# ESP32_SensorShield.net
KiCad netlist of a schematic drawn in EAGLE
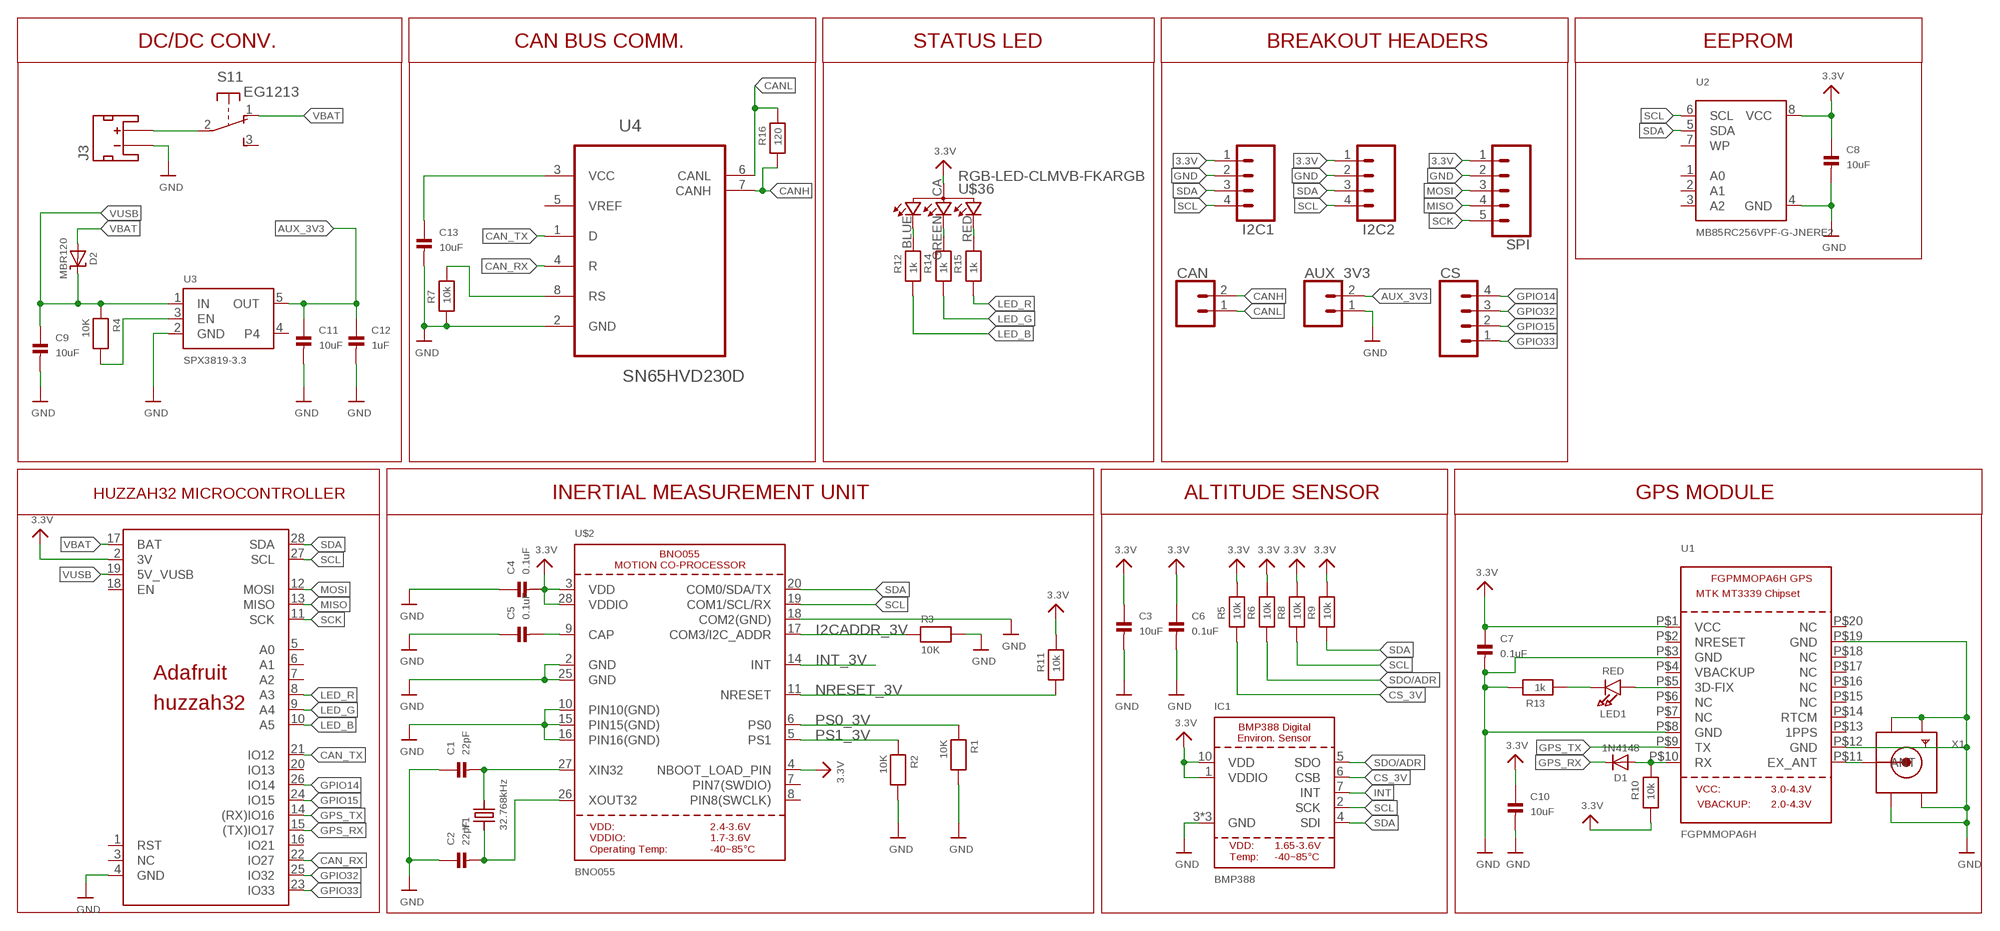
[diagram p0: schematic, sheet 1]

(export (version "E")
  (design (tool "Eeschema 10.0.6"))
  (components
    (comp (ref "AUX_3V3")
      (value "CONN_02")
      (footprint "eagle-import:1X02")
      (libsource (lib "eagle-import") (part "CONN_02"))
    )
    (comp (ref "C1")
      (value "22pF")
      (footprint "eagle-import:0603")
      (libsource (lib "eagle-import") (part "CAP_CERAMIC0603"))
    )
    (comp (ref "C2")
      (value "22pF")
      (footprint "eagle-import:0603")
      (libsource (lib "eagle-import") (part "CAP_CERAMIC0603"))
    )
    (comp (ref "C3")
      (value "10uF")
      (footprint "eagle-import:0805")
      (libsource (lib "eagle-import") (part "CAP_CERAMIC0805"))
    )
    (comp (ref "C4")
      (value "0.1uF")
      (footprint "eagle-import:0603")
      (libsource (lib "eagle-import") (part "CAP_CERAMIC0603"))
    )
    (comp (ref "C5")
      (value "0.1uF")
      (footprint "eagle-import:0603")
      (libsource (lib "eagle-import") (part "CAP_CERAMIC0603"))
    )
    (comp (ref "C6")
      (value "0.1uF")
      (footprint "eagle-import:0603")
      (libsource (lib "eagle-import") (part "CAP_CERAMIC0603"))
    )
    (comp (ref "C7")
      (value "0.1uF")
      (footprint "eagle-import:0603")
      (libsource (lib "eagle-import") (part "CAP_CERAMIC0603"))
    )
    (comp (ref "C8")
      (value "10uF")
      (footprint "eagle-import:0805")
      (libsource (lib "eagle-import") (part "CAP_CERAMIC0805"))
    )
    (comp (ref "C9")
      (value "10uF")
      (footprint "eagle-import:0805")
      (libsource (lib "eagle-import") (part "CAP_CERAMIC0805"))
    )
    (comp (ref "C10")
      (value "10uF")
      (footprint "eagle-import:0805")
      (libsource (lib "eagle-import") (part "CAP_CERAMIC0805"))
    )
    (comp (ref "C11")
      (value "10uF")
      (footprint "eagle-import:0805")
      (libsource (lib "eagle-import") (part "CAP_CERAMIC0805"))
    )
    (comp (ref "C12")
      (value "1uF")
      (footprint "eagle-import:0805")
      (libsource (lib "eagle-import") (part "CAP_CERAMIC0805"))
    )
    (comp (ref "C13")
      (value "10uF")
      (footprint "eagle-import:0805")
      (libsource (lib "eagle-import") (part "CAP_CERAMIC0805"))
    )
    (comp (ref "CAN")
      (value "CONN_02")
      (footprint "eagle-import:1X02")
      (libsource (lib "eagle-import") (part "CONN_02"))
    )
    (comp (ref "CS")
      (value "CONN_04")
      (footprint "eagle-import:1X04")
      (libsource (lib "eagle-import") (part "CONN_04"))
    )
    (comp (ref "D1")
      (value "1N4148")
      (footprint "eagle-import:SOD-323")
      (libsource (lib "eagle-import") (part "DIODESOD-323"))
    )
    (comp (ref "D2")
      (value "MBR120")
      (footprint "eagle-import:SOD-123")
      (libsource (lib "eagle-import") (part "DIODE-SCHOTTKYSOD-123"))
    )
    (comp (ref "I2C1")
      (value "CONN_04")
      (footprint "eagle-import:1X04")
      (libsource (lib "eagle-import") (part "CONN_04"))
    )
    (comp (ref "I2C2")
      (value "CONN_04")
      (footprint "eagle-import:1X04")
      (libsource (lib "eagle-import") (part "CONN_04"))
    )
    (comp (ref "IC1")
      (value "BMP388")
      (footprint "eagle-import:BMP388")
      (libsource (lib "eagle-import") (part "BMP388"))
    )
    (comp (ref "J3")
      (value "JST_2MM_MALE")
      (footprint "eagle-import:JST-2-SMD")
      (libsource (lib "eagle-import") (part "JST_2MM_MALE"))
    )
    (comp (ref "LED1")
      (value "RED")
      (footprint "eagle-import:CHIPLED_0805")
      (libsource (lib "eagle-import") (part "LED0805"))
    )
    (comp (ref "R1")
      (value "10K")
      (footprint "eagle-import:0603")
      (libsource (lib "eagle-import") (part "RESISTOR0603"))
    )
    (comp (ref "R2")
      (value "10K")
      (footprint "eagle-import:0603")
      (libsource (lib "eagle-import") (part "RESISTOR0603"))
    )
    (comp (ref "R3")
      (value "10K")
      (footprint "eagle-import:0603")
      (libsource (lib "eagle-import") (part "RESISTOR0603"))
    )
    (comp (ref "R4")
      (value "10K")
      (footprint "eagle-import:0603")
      (libsource (lib "eagle-import") (part "RESISTOR0603"))
    )
    (comp (ref "R5")
      (value "10k")
      (footprint "eagle-import:0603")
      (libsource (lib "eagle-import") (part "RESISTOR0603"))
    )
    (comp (ref "R6")
      (value "10k")
      (footprint "eagle-import:0603")
      (libsource (lib "eagle-import") (part "RESISTOR0603"))
    )
    (comp (ref "R7")
      (value "10k")
      (footprint "eagle-import:0603")
      (libsource (lib "eagle-import") (part "RESISTOR0603"))
    )
    (comp (ref "R8")
      (value "10k")
      (footprint "eagle-import:0603")
      (libsource (lib "eagle-import") (part "RESISTOR0603"))
    )
    (comp (ref "R9")
      (value "10k")
      (footprint "eagle-import:0603")
      (libsource (lib "eagle-import") (part "RESISTOR0603"))
    )
    (comp (ref "R10")
      (value "10k")
      (footprint "eagle-import:0603")
      (libsource (lib "eagle-import") (part "RESISTOR0603"))
    )
    (comp (ref "R11")
      (value "10k")
      (footprint "eagle-import:0603")
      (libsource (lib "eagle-import") (part "RESISTOR0603"))
    )
    (comp (ref "R12")
      (value "1k")
      (footprint "eagle-import:0603")
      (libsource (lib "eagle-import") (part "RESISTOR0603"))
    )
    (comp (ref "R13")
      (value "1k")
      (footprint "eagle-import:0603")
      (libsource (lib "eagle-import") (part "RESISTOR0603"))
    )
    (comp (ref "R14")
      (value "1k")
      (footprint "eagle-import:0603")
      (libsource (lib "eagle-import") (part "RESISTOR0603"))
    )
    (comp (ref "R15")
      (value "1k")
      (footprint "eagle-import:0603")
      (libsource (lib "eagle-import") (part "RESISTOR0603"))
    )
    (comp (ref "R16")
      (value "120")
      (footprint "eagle-import:0603")
      (libsource (lib "eagle-import") (part "RESISTOR0603"))
    )
    (comp (ref "S1")
      (value "EG1213")
      (footprint "eagle-import:EG1213")
      (libsource (lib "eagle-import") (part "EG1213"))
    )
    (comp (ref "SPI")
      (value "CONN_05")
      (footprint "eagle-import:1X05")
      (libsource (lib "eagle-import") (part "CONN_05"))
    )
    (comp (ref "U$1")
      (value "ADAFRUIT-FEATHER-HUZZAH32-SHIELD")
      (footprint "eagle-import:ADAFRUIT-FEATHER-HUZZAH32-SHIELD")
      (libsource (lib "eagle-import") (part "ADAFRUIT-FEATHER-HUZZAH32-SHIELD"))
    )
    (comp (ref "U$2")
      (value "BNO055")
      (footprint "eagle-import:BNO055")
      (libsource (lib "eagle-import") (part "BNO055"))
    )
    (comp (ref "U$36")
      (value "RGB-LED-CLMVB-FKARGB")
      (footprint "eagle-import:PLCC4-2MM-RGB")
      (libsource (lib "eagle-import") (part "RGB-LED-CLMVB-FKARGB"))
    )
    (comp (ref "U1")
      (value "FGPMMOPA6H")
      (footprint "eagle-import:FGPMMOPA6H")
      (libsource (lib "eagle-import") (part "GPS_FGPMMOPA6H"))
    )
    (comp (ref "U2")
      (value "MB85RC256VPF-G-JNERE2")
      (footprint "eagle-import:SOIC8_208MIL")
      (libsource (lib "eagle-import") (part "FRAM_SOIC8_I2C"))
    )
    (comp (ref "U3")
      (value "SPX3819-3.3")
      (footprint "eagle-import:SOT23-5")
      (libsource (lib "eagle-import") (part "VREG_SOT23-5"))
    )
    (comp (ref "U4")
      (value "SN65HVD230D")
      (footprint "eagle-import:SOIC127P600X175-8N")
      (fields (field (name "MF") "Texas Instruments"))
      (libsource (lib "eagle-import") (part "SN65HVD230D"))
    )
    (comp (ref "X1")
      (value "SMACONNECTOR_EDGE")
      (footprint "eagle-import:SMA_EDGELAUNCH")
      (libsource (lib "eagle-import") (part "SMACONNECTOR_EDGE"))
    )
    (comp (ref "Y1")
      (value "32.768kHz")
      (footprint "eagle-import:CRYSTAL_8X3.8")
      (libsource (lib "eagle-import") (part "CRYSTAL8.0X3.8"))
    )
  )
  (nets
    (net (code "1") (name "/I2CADDR_3V") (class "Default")
      (node (ref "R3") (pin "1") (pinfunction "1_1") (pintype "passive"))
      (node (ref "U$2") (pin "17") (pinfunction "COM3/I2C_ADDR_17") (pintype "bidirectional"))
    )
    (net (code "2") (name "/INT_3V") (class "Default")
      (node (ref "U$2") (pin "14") (pinfunction "INT_14") (pintype "output"))
    )
    (net (code "3") (name "/NRESET_3V") (class "Default")
      (node (ref "R11") (pin "1") (pinfunction "1_1") (pintype "passive"))
      (node (ref "U$2") (pin "11") (pinfunction "NRESET_11") (pintype "bidirectional"))
    )
    (net (code "4") (name "/PS0_3V") (class "Default")
      (node (ref "R1") (pin "1") (pinfunction "1_1") (pintype "passive"))
      (node (ref "U$2") (pin "6") (pinfunction "PS0_6") (pintype "input"))
    )
    (net (code "5") (name "/PS1_3V") (class "Default")
      (node (ref "R2") (pin "1") (pinfunction "1_1") (pintype "passive"))
      (node (ref "U$2") (pin "5") (pinfunction "PS1_5") (pintype "input"))
    )
    (net (code "6") (name "3.3V") (class "Default")
      (node (ref "C10") (pin "1") (pinfunction "P$1_1") (pintype "passive"))
      (node (ref "C3") (pin "1") (pinfunction "P$1_1") (pintype "passive"))
      (node (ref "C4") (pin "2") (pinfunction "P$2_2") (pintype "passive"))
      (node (ref "C6") (pin "1") (pinfunction "P$1_1") (pintype "passive"))
      (node (ref "C7") (pin "1") (pinfunction "P$1_1") (pintype "passive"))
      (node (ref "C8") (pin "1") (pinfunction "P$1_1") (pintype "passive"))
      (node (ref "I2C1") (pin "1") (pinfunction "1_1") (pintype "passive"))
      (node (ref "I2C2") (pin "1") (pinfunction "1_1") (pintype "passive"))
      (node (ref "IC1") (pin "1") (pinfunction "VDDIO_1") (pintype "power_in"))
      (node (ref "IC1") (pin "10") (pinfunction "VDD_10") (pintype "power_in"))
      (node (ref "R10") (pin "1") (pinfunction "1_1") (pintype "passive"))
      (node (ref "R11") (pin "2") (pinfunction "2_2") (pintype "passive"))
      (node (ref "R5") (pin "2") (pinfunction "2_2") (pintype "passive"))
      (node (ref "R6") (pin "2") (pinfunction "2_2") (pintype "passive"))
      (node (ref "R8") (pin "2") (pinfunction "2_2") (pintype "passive"))
      (node (ref "R9") (pin "2") (pinfunction "2_2") (pintype "passive"))
      (node (ref "SPI") (pin "1") (pinfunction "1_1") (pintype "passive"))
      (node (ref "U$1") (pin "2") (pinfunction "3V_2") (pintype "bidirectional"))
      (node (ref "U$2") (pin "28") (pinfunction "VDDIO_28") (pintype "power_in"))
      (node (ref "U$2") (pin "3") (pinfunction "VDD_3") (pintype "power_in"))
      (node (ref "U$2") (pin "4") (pinfunction "NBOOT_LOAD_PIN_4") (pintype "bidirectional"))
      (node (ref "U$36") (pin "CA") (pinfunction "1_CA") (pintype "passive"))
      (node (ref "U1") (pin "P$1") (pinfunction "VCC_P$1") (pintype "bidirectional"))
      (node (ref "U2") (pin "8") (pinfunction "VCC_8") (pintype "power_in"))
    )
    (net (code "7") (name "AUX_3V3") (class "Default")
      (node (ref "AUX_3V3") (pin "2") (pinfunction "2_2") (pintype "passive"))
      (node (ref "C11") (pin "1") (pinfunction "P$1_1") (pintype "passive"))
      (node (ref "C12") (pin "1") (pinfunction "P$1_1") (pintype "passive"))
      (node (ref "U3") (pin "5") (pinfunction "OUT_5") (pintype "power_in"))
    )
    (net (code "8") (name "CANH") (class "Default")
      (node (ref "CAN") (pin "2") (pinfunction "2_2") (pintype "passive"))
      (node (ref "R16") (pin "1") (pinfunction "1_1") (pintype "passive"))
      (node (ref "U4") (pin "7") (pinfunction "CANH_7") (pintype "output"))
    )
    (net (code "9") (name "CANL") (class "Default")
      (node (ref "CAN") (pin "1") (pinfunction "1_1") (pintype "passive"))
      (node (ref "R16") (pin "2") (pinfunction "2_2") (pintype "passive"))
      (node (ref "U4") (pin "6") (pinfunction "CANL_6") (pintype "output"))
    )
    (net (code "10") (name "CAN_RX") (class "Default")
      (node (ref "U$1") (pin "22") (pinfunction "IO27_22") (pintype "bidirectional"))
      (node (ref "U4") (pin "4") (pinfunction "R_4") (pintype "input"))
    )
    (net (code "11") (name "CAN_TX") (class "Default")
      (node (ref "U$1") (pin "21") (pinfunction "IO12_21") (pintype "bidirectional"))
      (node (ref "U4") (pin "1") (pinfunction "D_1") (pintype "input"))
    )
    (net (code "12") (name "CS_3V") (class "Default")
      (node (ref "IC1") (pin "6") (pinfunction "CSB_6") (pintype "input"))
      (node (ref "R5") (pin "1") (pinfunction "1_1") (pintype "passive"))
    )
    (net (code "13") (name "GND") (class "Default")
      (node (ref "AUX_3V3") (pin "1") (pinfunction "1_1") (pintype "passive"))
      (node (ref "C1") (pin "1") (pinfunction "P$1_1") (pintype "passive"))
      (node (ref "C10") (pin "2") (pinfunction "P$2_2") (pintype "passive"))
      (node (ref "C11") (pin "2") (pinfunction "P$2_2") (pintype "passive"))
      (node (ref "C12") (pin "2") (pinfunction "P$2_2") (pintype "passive"))
      (node (ref "C13") (pin "2") (pinfunction "P$2_2") (pintype "passive"))
      (node (ref "C2") (pin "1") (pinfunction "P$1_1") (pintype "passive"))
      (node (ref "C3") (pin "2") (pinfunction "P$2_2") (pintype "passive"))
      (node (ref "C4") (pin "1") (pinfunction "P$1_1") (pintype "passive"))
      (node (ref "C5") (pin "1") (pinfunction "P$1_1") (pintype "passive"))
      (node (ref "C6") (pin "2") (pinfunction "P$2_2") (pintype "passive"))
      (node (ref "C7") (pin "2") (pinfunction "P$2_2") (pintype "passive"))
      (node (ref "C8") (pin "2") (pinfunction "P$2_2") (pintype "passive"))
      (node (ref "C9") (pin "2") (pinfunction "P$2_2") (pintype "passive"))
      (node (ref "I2C1") (pin "2") (pinfunction "2_2") (pintype "passive"))
      (node (ref "I2C2") (pin "2") (pinfunction "2_2") (pintype "passive"))
      (node (ref "IC1") (pin "3") (pinfunction "GND_3") (pintype "power_in"))
      (node (ref "IC1") (pin "8") (pinfunction "GND_8") (pintype "power_in"))
      (node (ref "IC1") (pin "9") (pinfunction "GND_9") (pintype "power_in"))
      (node (ref "J3") (pin "1") (pinfunction "-_1") (pintype "bidirectional"))
      (node (ref "R1") (pin "2") (pinfunction "2_2") (pintype "passive"))
      (node (ref "R13") (pin "2") (pinfunction "2_2") (pintype "passive"))
      (node (ref "R2") (pin "2") (pinfunction "2_2") (pintype "passive"))
      (node (ref "R3") (pin "2") (pinfunction "2_2") (pintype "passive"))
      (node (ref "R7") (pin "1") (pinfunction "1_1") (pintype "passive"))
      (node (ref "SPI") (pin "2") (pinfunction "2_2") (pintype "passive"))
      (node (ref "U$1") (pin "4") (pinfunction "GND_4") (pintype "power_in"))
      (node (ref "U$2") (pin "10") (pinfunction "PIN10(GND)_10") (pintype "bidirectional"))
      (node (ref "U$2") (pin "15") (pinfunction "PIN15(GND)_15") (pintype "bidirectional"))
      (node (ref "U$2") (pin "16") (pinfunction "PIN16(GND)_16") (pintype "bidirectional"))
      (node (ref "U$2") (pin "18") (pinfunction "COM2(GND)_18") (pintype "bidirectional"))
      (node (ref "U$2") (pin "2") (pinfunction "GND_2") (pintype "power_in"))
      (node (ref "U$2") (pin "25") (pinfunction "GND_25") (pintype "power_in"))
      (node (ref "U1") (pin "P$12") (pinfunction "GND_P$12") (pintype "bidirectional"))
      (node (ref "U1") (pin "P$19") (pinfunction "GND_P$19") (pintype "bidirectional"))
      (node (ref "U1") (pin "P$3") (pinfunction "GND_P$3") (pintype "bidirectional"))
      (node (ref "U1") (pin "P$8") (pinfunction "GND_P$8") (pintype "bidirectional"))
      (node (ref "U2") (pin "4") (pinfunction "GND_4") (pintype "power_in"))
      (node (ref "U3") (pin "2") (pinfunction "GND_2") (pintype "power_in"))
      (node (ref "U4") (pin "2") (pinfunction "GND_2") (pintype "passive"))
      (node (ref "X1") (pin "GND@1") (pinfunction "GND4_GND@1") (pintype "power_in"))
      (node (ref "X1") (pin "GND@2") (pinfunction "GND3_GND@2") (pintype "power_in"))
      (node (ref "X1") (pin "GND@3") (pinfunction "GND2_GND@3") (pintype "power_in"))
      (node (ref "X1") (pin "GND@4") (pinfunction "GND1_GND@4") (pintype "power_in"))
    )
    (net (code "14") (name "GPIO14") (class "Default")
      (node (ref "CS") (pin "4") (pinfunction "4_4") (pintype "passive"))
      (node (ref "U$1") (pin "26") (pinfunction "IO14_26") (pintype "bidirectional"))
    )
    (net (code "15") (name "GPIO15") (class "Default")
      (node (ref "CS") (pin "2") (pinfunction "2_2") (pintype "passive"))
      (node (ref "U$1") (pin "24") (pinfunction "IO15_24") (pintype "bidirectional"))
    )
    (net (code "16") (name "GPIO32") (class "Default")
      (node (ref "CS") (pin "3") (pinfunction "3_3") (pintype "passive"))
      (node (ref "U$1") (pin "25") (pinfunction "IO32_25") (pintype "bidirectional"))
    )
    (net (code "17") (name "GPIO33") (class "Default")
      (node (ref "CS") (pin "1") (pinfunction "1_1") (pintype "passive"))
      (node (ref "U$1") (pin "23") (pinfunction "IO33_23") (pintype "bidirectional"))
    )
    (net (code "18") (name "GPS_RX") (class "Default")
      (node (ref "D1") (pin "C") (pinfunction "C_C") (pintype "passive"))
      (node (ref "U$1") (pin "15") (pinfunction "(TX)IO17_15") (pintype "bidirectional"))
    )
    (net (code "19") (name "GPS_TX") (class "Default")
      (node (ref "U$1") (pin "14") (pinfunction "(RX)IO16_14") (pintype "bidirectional"))
      (node (ref "U1") (pin "P$9") (pinfunction "TX_P$9") (pintype "bidirectional"))
    )
    (net (code "20") (name "INT") (class "Default")
      (node (ref "IC1") (pin "7") (pinfunction "INT_7") (pintype "output"))
    )
    (net (code "21") (name "LED_B") (class "Default")
      (node (ref "R12") (pin "1") (pinfunction "1_1") (pintype "passive"))
      (node (ref "U$1") (pin "10") (pinfunction "A5_10") (pintype "bidirectional"))
    )
    (net (code "22") (name "LED_G") (class "Default")
      (node (ref "R14") (pin "1") (pinfunction "1_1") (pintype "passive"))
      (node (ref "U$1") (pin "9") (pinfunction "A4_9") (pintype "bidirectional"))
    )
    (net (code "23") (name "LED_R") (class "Default")
      (node (ref "R15") (pin "1") (pinfunction "1_1") (pintype "passive"))
      (node (ref "U$1") (pin "8") (pinfunction "A3_8") (pintype "bidirectional"))
    )
    (net (code "24") (name "MISO") (class "Default")
      (node (ref "SPI") (pin "4") (pinfunction "4_4") (pintype "passive"))
      (node (ref "U$1") (pin "13") (pinfunction "MISO_13") (pintype "bidirectional"))
    )
    (net (code "25") (name "MOSI") (class "Default")
      (node (ref "SPI") (pin "3") (pinfunction "3_3") (pintype "passive"))
      (node (ref "U$1") (pin "12") (pinfunction "MOSI_12") (pintype "bidirectional"))
    )
    (net (code "26") (name "Net-(C1-P$2)") (class "Default")
      (node (ref "C1") (pin "2") (pinfunction "P$2_2") (pintype "passive"))
      (node (ref "U$2") (pin "27") (pinfunction "XIN32_27") (pintype "input"))
      (node (ref "Y1") (pin "P$4") (pinfunction "2_P$4") (pintype "passive"))
    )
    (net (code "27") (name "Net-(C2-P$2)") (class "Default")
      (node (ref "C2") (pin "2") (pinfunction "P$2_2") (pintype "passive"))
      (node (ref "U$2") (pin "26") (pinfunction "XOUT32_26") (pintype "output"))
      (node (ref "Y1") (pin "P$1") (pinfunction "1_P$1") (pintype "passive"))
    )
    (net (code "28") (name "Net-(C5-P$2)") (class "Default")
      (node (ref "C5") (pin "2") (pinfunction "P$2_2") (pintype "passive"))
      (node (ref "U$2") (pin "9") (pinfunction "CAP_9") (pintype "passive"))
    )
    (net (code "29") (name "Net-(C13-P$1)") (class "Default")
      (node (ref "C13") (pin "1") (pinfunction "P$1_1") (pintype "passive"))
      (node (ref "U4") (pin "3") (pinfunction "VCC_3") (pintype "power_in"))
    )
    (net (code "30") (name "Net-(J3-+)") (class "Default")
      (node (ref "J3") (pin "2") (pinfunction "+_2") (pintype "bidirectional"))
      (node (ref "S1") (pin "2") (pinfunction "P_2") (pintype "passive"))
    )
    (net (code "31") (name "Net-(LED1-PadC)") (class "Default")
      (node (ref "LED1") (pin "C") (pinfunction "C_C") (pintype "passive"))
      (node (ref "R13") (pin "1") (pinfunction "1_1") (pintype "passive"))
    )
    (net (code "32") (name "Net-(U$36-2)") (class "Default")
      (node (ref "R12") (pin "2") (pinfunction "2_2") (pintype "passive"))
      (node (ref "U$36") (pin "BLUE") (pinfunction "2_BLUE") (pintype "passive"))
    )
    (net (code "33") (name "Net-(U$36-3)") (class "Default")
      (node (ref "R14") (pin "2") (pinfunction "2_2") (pintype "passive"))
      (node (ref "U$36") (pin "GREEN") (pinfunction "3_GREEN") (pintype "passive"))
    )
    (net (code "34") (name "Net-(U$36-4)") (class "Default")
      (node (ref "R15") (pin "2") (pinfunction "2_2") (pintype "passive"))
      (node (ref "U$36") (pin "RED") (pinfunction "4_RED") (pintype "passive"))
    )
    (net (code "35") (name "Net-(U1-3D-FIX)") (class "Default")
      (node (ref "LED1") (pin "A") (pinfunction "A_A") (pintype "passive"))
      (node (ref "U1") (pin "P$5") (pinfunction "3D-FIX_P$5") (pintype "bidirectional"))
    )
    (net (code "36") (name "Net-(U1-EX_ANT)") (class "Default")
      (node (ref "U1") (pin "P$11") (pinfunction "EX_ANT_P$11") (pintype "bidirectional"))
      (node (ref "X1") (pin "P") (pinfunction "ANT_P") (pintype "bidirectional"))
    )
    (net (code "37") (name "Net-(U1-RX)") (class "Default")
      (node (ref "D1") (pin "A") (pinfunction "A_A") (pintype "passive"))
      (node (ref "R10") (pin "2") (pinfunction "2_2") (pintype "passive"))
      (node (ref "U1") (pin "P$10") (pinfunction "RX_P$10") (pintype "bidirectional"))
    )
    (net (code "38") (name "Net-(U3-EN)") (class "Default")
      (node (ref "R4") (pin "2") (pinfunction "2_2") (pintype "passive"))
      (node (ref "U3") (pin "3") (pinfunction "EN_3") (pintype "input"))
    )
    (net (code "39") (name "Net-(U4-RS)") (class "Default")
      (node (ref "R7") (pin "2") (pinfunction "2_2") (pintype "passive"))
      (node (ref "U4") (pin "8") (pinfunction "RS_8") (pintype "input"))
    )
    (net (code "40") (name "SCK") (class "Default")
      (node (ref "SPI") (pin "5") (pinfunction "5_5") (pintype "passive"))
      (node (ref "U$1") (pin "11") (pinfunction "SCK_11") (pintype "bidirectional"))
    )
    (net (code "41") (name "SCL") (class "Default")
      (node (ref "I2C1") (pin "4") (pinfunction "4_4") (pintype "passive"))
      (node (ref "I2C2") (pin "4") (pinfunction "4_4") (pintype "passive"))
      (node (ref "IC1") (pin "2") (pinfunction "SCK_2") (pintype "input"))
      (node (ref "R8") (pin "1") (pinfunction "1_1") (pintype "passive"))
      (node (ref "U$1") (pin "27") (pinfunction "SCL_27") (pintype "bidirectional"))
      (node (ref "U$2") (pin "19") (pinfunction "COM1/SCL/RX_19") (pintype "bidirectional"))
      (node (ref "U2") (pin "6") (pinfunction "SCL_6") (pintype "input"))
    )
    (net (code "42") (name "SDA") (class "Default")
      (node (ref "I2C1") (pin "3") (pinfunction "3_3") (pintype "passive"))
      (node (ref "I2C2") (pin "3") (pinfunction "3_3") (pintype "passive"))
      (node (ref "IC1") (pin "4") (pinfunction "SDI_4") (pintype "input"))
      (node (ref "R9") (pin "1") (pinfunction "1_1") (pintype "passive"))
      (node (ref "U$1") (pin "28") (pinfunction "SDA_28") (pintype "bidirectional"))
      (node (ref "U$2") (pin "20") (pinfunction "COM0/SDA/TX_20") (pintype "bidirectional"))
      (node (ref "U2") (pin "5") (pinfunction "SDA_5") (pintype "bidirectional"))
    )
    (net (code "43") (name "SDO{slash}ADR") (class "Default")
      (node (ref "IC1") (pin "5") (pinfunction "SDO_5") (pintype "output"))
      (node (ref "R6") (pin "1") (pinfunction "1_1") (pintype "passive"))
    )
    (net (code "44") (name "VBAT") (class "Default")
      (node (ref "D2") (pin "A") (pinfunction "A_A") (pintype "passive"))
      (node (ref "S1") (pin "1") (pinfunction "O_1") (pintype "passive"))
      (node (ref "U$1") (pin "17") (pinfunction "BAT_17") (pintype "bidirectional"))
    )
    (net (code "45") (name "VUSB") (class "Default")
      (node (ref "C9") (pin "1") (pinfunction "P$1_1") (pintype "passive"))
      (node (ref "D2") (pin "C") (pinfunction "C_C") (pintype "passive"))
      (node (ref "R4") (pin "1") (pinfunction "1_1") (pintype "passive"))
      (node (ref "U$1") (pin "19") (pinfunction "5V_VUSB_19") (pintype "bidirectional"))
      (node (ref "U3") (pin "1") (pinfunction "IN_1") (pintype "power_in"))
    )
    (net (code "46") (name "unconnected-(J3-PAD1-PadNC1)") (class "Default")
      (node (ref "J3") (pin "NC1") (pinfunction "PAD1_NC1") (pintype "bidirectional"))
    )
    (net (code "47") (name "unconnected-(J3-PAD2-PadNC2)") (class "Default")
      (node (ref "J3") (pin "NC2") (pinfunction "PAD2_NC2") (pintype "bidirectional"))
    )
    (net (code "48") (name "unconnected-(S1A-S-Pad3)") (class "Default")
      (node (ref "S1") (pin "3") (pinfunction "S_3") (pintype "passive"))
    )
    (net (code "49") (name "unconnected-(U$1-A0-Pad5)") (class "Default")
      (node (ref "U$1") (pin "5") (pinfunction "A0_5") (pintype "bidirectional"))
    )
    (net (code "50") (name "unconnected-(U$1-A1-Pad6)") (class "Default")
      (node (ref "U$1") (pin "6") (pinfunction "A1_6") (pintype "bidirectional"))
    )
    (net (code "51") (name "unconnected-(U$1-A2-Pad7)") (class "Default")
      (node (ref "U$1") (pin "7") (pinfunction "A2_7") (pintype "bidirectional"))
    )
    (net (code "52") (name "unconnected-(U$1-EN-Pad18)") (class "Default")
      (node (ref "U$1") (pin "18") (pinfunction "EN_18") (pintype "bidirectional"))
    )
    (net (code "53") (name "unconnected-(U$1-IO13-Pad20)") (class "Default")
      (node (ref "U$1") (pin "20") (pinfunction "IO13_20") (pintype "bidirectional"))
    )
    (net (code "54") (name "unconnected-(U$1-IO21-Pad16)") (class "Default")
      (node (ref "U$1") (pin "16") (pinfunction "IO21_16") (pintype "bidirectional"))
    )
    (net (code "55") (name "unconnected-(U$1-NC-Pad3)") (class "Default")
      (node (ref "U$1") (pin "3") (pinfunction "NC_3") (pintype "no_connect"))
    )
    (net (code "56") (name "unconnected-(U$1-RST-Pad1)") (class "Default")
      (node (ref "U$1") (pin "1") (pinfunction "RST_1") (pintype "no_connect"))
    )
    (net (code "57") (name "unconnected-(U$2-PIN7(SWDIO)-Pad7)") (class "Default")
      (node (ref "U$2") (pin "7") (pinfunction "PIN7(SWDIO)_7") (pintype "bidirectional"))
    )
    (net (code "58") (name "unconnected-(U$2-PIN8(SWCLK)-Pad8)") (class "Default")
      (node (ref "U$2") (pin "8") (pinfunction "PIN8(SWCLK)_8") (pintype "bidirectional"))
    )
    (net (code "59") (name "unconnected-(U1-1PPS-PadP$13)") (class "Default")
      (node (ref "U1") (pin "P$13") (pinfunction "1PPS_P$13") (pintype "bidirectional"))
    )
    (net (code "60") (name "unconnected-(U1-NC-PadP$6)") (class "Default")
      (node (ref "U1") (pin "P$6") (pinfunction "NC_P$6") (pintype "bidirectional"))
    )
    (net (code "61") (name "unconnected-(U1-NC-PadP$7)") (class "Default")
      (node (ref "U1") (pin "P$7") (pinfunction "NC_P$7") (pintype "bidirectional"))
    )
    (net (code "62") (name "unconnected-(U1-NC-PadP$15)") (class "Default")
      (node (ref "U1") (pin "P$15") (pinfunction "NC_P$15") (pintype "bidirectional"))
    )
    (net (code "63") (name "unconnected-(U1-NC-PadP$16)") (class "Default")
      (node (ref "U1") (pin "P$16") (pinfunction "NC_P$16") (pintype "bidirectional"))
    )
    (net (code "64") (name "unconnected-(U1-NC-PadP$17)") (class "Default")
      (node (ref "U1") (pin "P$17") (pinfunction "NC_P$17") (pintype "bidirectional"))
    )
    (net (code "65") (name "unconnected-(U1-NC-PadP$18)") (class "Default")
      (node (ref "U1") (pin "P$18") (pinfunction "NC_P$18") (pintype "bidirectional"))
    )
    (net (code "66") (name "unconnected-(U1-NC-PadP$20)") (class "Default")
      (node (ref "U1") (pin "P$20") (pinfunction "NC_P$20") (pintype "bidirectional"))
    )
    (net (code "67") (name "unconnected-(U1-NRESET-PadP$2)") (class "Default")
      (node (ref "U1") (pin "P$2") (pinfunction "NRESET_P$2") (pintype "bidirectional"))
    )
    (net (code "68") (name "unconnected-(U1-RTCM-PadP$14)") (class "Default")
      (node (ref "U1") (pin "P$14") (pinfunction "RTCM_P$14") (pintype "bidirectional"))
    )
    (net (code "69") (name "unconnected-(U1-VBACKUP-PadP$4)") (class "Default")
      (node (ref "U1") (pin "P$4") (pinfunction "VBACKUP_P$4") (pintype "bidirectional"))
    )
    (net (code "70") (name "unconnected-(U2-A0-Pad1)") (class "Default")
      (node (ref "U2") (pin "1") (pinfunction "A0_1") (pintype "input"))
    )
    (net (code "71") (name "unconnected-(U2-A1-Pad2)") (class "Default")
      (node (ref "U2") (pin "2") (pinfunction "A1_2") (pintype "input"))
    )
    (net (code "72") (name "unconnected-(U2-A2-Pad3)") (class "Default")
      (node (ref "U2") (pin "3") (pinfunction "A2_3") (pintype "input"))
    )
    (net (code "73") (name "unconnected-(U2-WP-Pad7)") (class "Default")
      (node (ref "U2") (pin "7") (pinfunction "WP_7") (pintype "input"))
    )
    (net (code "74") (name "unconnected-(U3-P4-Pad4)") (class "Default")
      (node (ref "U3") (pin "4") (pinfunction "P4_4") (pintype "bidirectional"))
    )
    (net (code "75") (name "unconnected-(U4-VREF-Pad5)") (class "Default")
      (node (ref "U4") (pin "5") (pinfunction "VREF_5") (pintype "input"))
    )
  )
)
